# ValveControl.net
KiCad netlist of a schematic drawn in Altium Designer
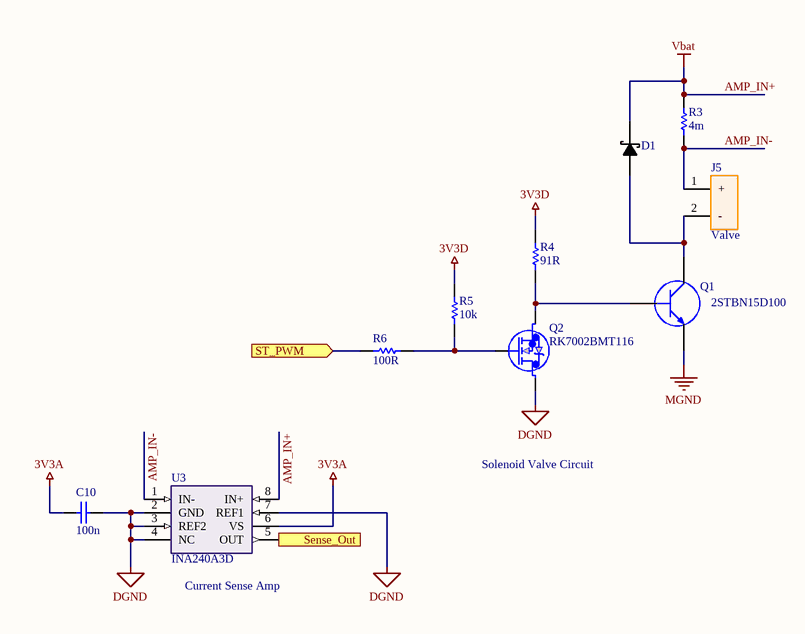
[diagram p0: ValveControl.SchDoc]

(export (version "E")
  (design (tool "Eeschema 10.0.6"))
  (components
    (comp (ref "C10")
      (value "100n")
      (footprint "C0603_med_density")
      (description "SMD Ceramic Capacitor")
      (fields (field (name "Comment") "CapCer"))
      (libsource (lib "passives") (part "CapCer"))
    )
    (comp (ref "D1")
      (value "1655-1921-1-ND")
      (footprint "DO-201AD")
      (description "Schottky Diode")
      (libsource (lib "passives") (part "DiodeSchottky"))
    )
    (comp (ref "J5")
      (value "Valve")
      (footprint "MOLEX_436500200 - duplicate")
      (libsource (lib "connectors") (part "General Molex"))
    )
    (comp (ref "Q1")
      (value "2STBN15D100")
      (footprint "D2PAK")
      (description "2STBN15D100 BJT")
      (libsource (lib "valves") (part "BJT"))
    )
    (comp (ref "Q2")
      (value "RK7002BMT116")
      (footprint "TRANS_RK7002BMHZG_ROM")
      (description "n-channel MOSEFT")
      (fields (field (name "COPYRIGHT") "Copyright (C) 2018 Accelerated Designs. All rights reserved"))
      (libsource (lib "valves") (part "RK7002BMT116"))
    )
    (comp (ref "R3")
      (value "4m")
      (footprint "R1210_med_density")
      (description "SMD Chip resistor")
      (fields (field (name "TOLERANCE") "1%") (field (name "Comment") "ResChip"))
      (libsource (lib "passives") (part "ResChip"))
    )
    (comp (ref "R4")
      (value "91R")
      (footprint "R0603_med_density")
      (description "SMD Chip resistor")
      (fields (field (name "TOLERANCE") "1%") (field (name "Comment") "ResChip"))
      (libsource (lib "passives") (part "ResChip"))
    )
    (comp (ref "R5")
      (value "10k")
      (footprint "R0603_med_density")
      (description "SMD Chip resistor")
      (fields (field (name "Comment") "ResChip"))
      (libsource (lib "passives") (part "ResChip"))
    )
    (comp (ref "R6")
      (value "100R")
      (footprint "R0603_med_density")
      (description "SMD Chip resistor")
      (fields (field (name "Comment") "ResChip"))
      (libsource (lib "passives") (part "ResChip"))
    )
    (comp (ref "U3")
      (value "INA240A3D")
      (footprint "INA240A3D")
      (description "SchLib for TI op amp for current sensing.")
      (libsource (lib "valves") (part "INA240A3D"))
    )
  )
  (nets
    (net (code "1") (name "/AMP_IN-") (class "Default")
      (node (ref "J5") (pin "1") (pinfunction "+_1") (pintype "passive"))
      (node (ref "R3") (pin "1") (pinfunction "1_1") (pintype "passive"))
      (node (ref "U3") (pin "1") (pinfunction "IN-_1") (pintype "input"))
    )
    (net (code "2") (name "/ST_PWM") (class "Default")
      (node (ref "R6") (pin "2") (pinfunction "2_2") (pintype "passive"))
    )
    (net (code "3") (name "/Sense_Out") (class "Default")
      (node (ref "U3") (pin "5") (pinfunction "OUT_5") (pintype "output"))
    )
    (net (code "4") (name "3V3A") (class "Default")
      (node (ref "C10") (pin "1") (pinfunction "1_1") (pintype "passive"))
      (node (ref "U3") (pin "6") (pinfunction "VS_6") (pintype "passive"))
    )
    (net (code "5") (name "3V3D") (class "Default")
      (node (ref "R4") (pin "1") (pinfunction "1_1") (pintype "passive"))
      (node (ref "R5") (pin "1") (pinfunction "1_1") (pintype "passive"))
    )
    (net (code "6") (name "DGND") (class "Default")
      (node (ref "C10") (pin "2") (pinfunction "2_2") (pintype "passive"))
      (node (ref "Q2") (pin "1") (pinfunction "2_1") (pintype "passive"))
      (node (ref "U3") (pin "2") (pinfunction "GND_2") (pintype "passive"))
      (node (ref "U3") (pin "3") (pinfunction "REF2_3") (pintype "input"))
      (node (ref "U3") (pin "4") (pinfunction "NC_4") (pintype "passive"))
      (node (ref "U3") (pin "7") (pinfunction "REF1_7") (pintype "input"))
    )
    (net (code "7") (name "MGND") (class "Default")
      (node (ref "Q1") (pin "3") (pinfunction "B_3") (pintype "passive"))
    )
    (net (code "8") (name "Net-(J5--)") (class "Default")
      (node (ref "D1") (pin "1") (pinfunction "1_1") (pintype "passive"))
      (node (ref "J5") (pin "2") (pinfunction "-_2") (pintype "passive"))
      (node (ref "Q1") (pin "1") (pinfunction "B_1") (pintype "passive"))
    )
    (net (code "9") (name "Net-(Q1-B-Pad2)") (class "Default")
      (node (ref "Q1") (pin "2") (pinfunction "B_2") (pintype "passive"))
      (node (ref "Q2") (pin "3") (pinfunction "3_3") (pintype "passive"))
      (node (ref "R4") (pin "2") (pinfunction "2_2") (pintype "passive"))
    )
    (net (code "10") (name "Net-(Q2-1)") (class "Default")
      (node (ref "Q2") (pin "2") (pinfunction "1_2") (pintype "passive"))
      (node (ref "R5") (pin "2") (pinfunction "2_2") (pintype "passive"))
      (node (ref "R6") (pin "1") (pinfunction "1_1") (pintype "passive"))
    )
    (net (code "11") (name "Vbat") (class "Default")
      (node (ref "D1") (pin "2") (pinfunction "2_2") (pintype "passive"))
      (node (ref "R3") (pin "2") (pinfunction "2_2") (pintype "passive"))
      (node (ref "U3") (pin "8") (pinfunction "IN+_8") (pintype "input"))
    )
  )
)
